# butt_blaster_mk_2.net
KiCad netlist of a schematic drawn in EAGLE
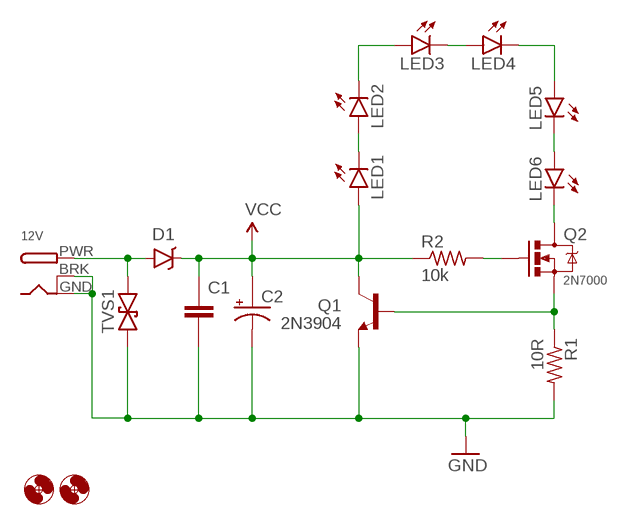
[diagram p0: schematic, sheet 1]

(export (version "E")
  (design (tool "Eeschema 10.0.6"))
  (components
    (comp (ref "12V")
      (value "DCBARRELPTH")
      (footprint "eagle-import:DCJACK_2MM_PTH")
      (libsource (lib "eagle-import") (part "DCBARRELPTH"))
    )
    (comp (ref "C1")
      (value "CAPACITOR-CERAMIC025-024X044")
      (footprint "eagle-import:C025-024X044")
      (libsource (lib "eagle-import") (part "CAPACITOR-CERAMIC025-024X044"))
    )
    (comp (ref "C2")
      (value "CAPACITOR-POLARIZEDE2.5-6")
      (footprint "eagle-import:E2,5-6")
      (libsource (lib "eagle-import") (part "CAPACITOR-POLARIZEDE2.5-6"))
    )
    (comp (ref "D1")
      (value "DIODE-SCHOTTKYPTH-8.38MM")
      (footprint "eagle-import:DIODE-8.38MM")
      (libsource (lib "eagle-import") (part "DIODE-SCHOTTKYPTH-8.38MM"))
    )
    (comp (ref "H1")
      (value "HOLE#2")
      (footprint "eagle-import:HOLE-#2")
      (libsource (lib "eagle-import") (part "HOLE#2"))
    )
    (comp (ref "H2")
      (value "HOLE#2")
      (footprint "eagle-import:HOLE-#2")
      (libsource (lib "eagle-import") (part "HOLE#2"))
    )
    (comp (ref "LED1")
      (value "LED5MM_SHORTPADS")
      (footprint "eagle-import:LED5MM_SHORTPADS")
      (libsource (lib "eagle-import") (part "LED5MM_SHORTPADS"))
    )
    (comp (ref "LED2")
      (value "LED5MM_SHORTPADS")
      (footprint "eagle-import:LED5MM_SHORTPADS")
      (libsource (lib "eagle-import") (part "LED5MM_SHORTPADS"))
    )
    (comp (ref "LED3")
      (value "LED5MM_SHORTPADS")
      (footprint "eagle-import:LED5MM_SHORTPADS")
      (libsource (lib "eagle-import") (part "LED5MM_SHORTPADS"))
    )
    (comp (ref "LED4")
      (value "LED5MM_SHORTPADS")
      (footprint "eagle-import:LED5MM_SHORTPADS")
      (libsource (lib "eagle-import") (part "LED5MM_SHORTPADS"))
    )
    (comp (ref "LED5")
      (value "LED5MM_SHORTPADS")
      (footprint "eagle-import:LED5MM_SHORTPADS")
      (libsource (lib "eagle-import") (part "LED5MM_SHORTPADS"))
    )
    (comp (ref "LED6")
      (value "LED5MM_SHORTPADS")
      (footprint "eagle-import:LED5MM_SHORTPADS")
      (libsource (lib "eagle-import") (part "LED5MM_SHORTPADS"))
    )
    (comp (ref "Q1")
      (value "2N3904")
      (footprint "eagle-import:TO-92-AMMO")
      (libsource (lib "eagle-import") (part "TRANSISTOR_NPNTO-92-AMMO-EBC"))
    )
    (comp (ref "Q2")
      (value "2N7000")
      (footprint "eagle-import:TO-92-AMMO")
      (libsource (lib "eagle-import") (part "MOSFET-NCHANNEL2N7000-AMMO"))
    )
    (comp (ref "R1")
      (value "10R")
      (footprint "eagle-import:RESISTOR-AXIAL-PTH-7.68MM")
      (libsource (lib "eagle-import") (part "RESISTORPTH-AXIAL-7.68MM"))
    )
    (comp (ref "R2")
      (value "10k")
      (footprint "eagle-import:RESISTOR-AXIAL-PTH-7.68MM")
      (libsource (lib "eagle-import") (part "RESISTORPTH-AXIAL-7.68MM"))
    )
    (comp (ref "TVS1")
      (value "TVSDO-41-TVS-BIDIRECTIONAL")
      (footprint "eagle-import:DO-41-TVS")
      (libsource (lib "eagle-import") (part "TVSDO-41-TVS-BIDIRECTIONAL"))
    )
  )
  (nets
    (net (code "1") (name "GND") (class "Default")
      (node (ref "12V") (pin "BRK") (pinfunction "BRK_BRK") (pintype "power_in"))
      (node (ref "12V") (pin "GND") (pinfunction "GND_GND") (pintype "power_in"))
      (node (ref "C1") (pin "2") (pinfunction "2_2") (pintype "passive"))
      (node (ref "C2") (pin "-") (pinfunction "-_-") (pintype "passive"))
      (node (ref "Q1") (pin "1") (pinfunction "E_1") (pintype "passive"))
      (node (ref "R1") (pin "P$2") (pinfunction "2_P$2") (pintype "passive"))
      (node (ref "TVS1") (pin "P$1") (pinfunction "1_P$1") (pintype "passive"))
    )
    (net (code "2") (name "Net-(LED1-C)") (class "Default")
      (node (ref "LED1") (pin "K") (pinfunction "C_K") (pintype "passive"))
      (node (ref "LED2") (pin "A") (pinfunction "A_A") (pintype "passive"))
    )
    (net (code "3") (name "Net-(LED2-C)") (class "Default")
      (node (ref "LED2") (pin "K") (pinfunction "C_K") (pintype "passive"))
      (node (ref "LED3") (pin "A") (pinfunction "A_A") (pintype "passive"))
    )
    (net (code "4") (name "Net-(LED3-C)") (class "Default")
      (node (ref "LED3") (pin "K") (pinfunction "C_K") (pintype "passive"))
      (node (ref "LED4") (pin "A") (pinfunction "A_A") (pintype "passive"))
    )
    (net (code "5") (name "Net-(LED4-C)") (class "Default")
      (node (ref "LED4") (pin "K") (pinfunction "C_K") (pintype "passive"))
      (node (ref "LED5") (pin "A") (pinfunction "A_A") (pintype "passive"))
    )
    (net (code "6") (name "Net-(LED5-C)") (class "Default")
      (node (ref "LED5") (pin "K") (pinfunction "C_K") (pintype "passive"))
      (node (ref "LED6") (pin "A") (pinfunction "A_A") (pintype "passive"))
    )
    (net (code "7") (name "Net-(LED6-C)") (class "Default")
      (node (ref "LED6") (pin "K") (pinfunction "C_K") (pintype "passive"))
      (node (ref "Q2") (pin "3") (pinfunction "D_3") (pintype "passive"))
    )
    (net (code "8") (name "Net-(Q1-B)") (class "Default")
      (node (ref "Q1") (pin "2") (pinfunction "B_2") (pintype "passive"))
      (node (ref "Q2") (pin "1") (pinfunction "S_1") (pintype "passive"))
      (node (ref "R1") (pin "P$1") (pinfunction "1_P$1") (pintype "passive"))
    )
    (net (code "9") (name "Net-(Q2-G)") (class "Default")
      (node (ref "Q2") (pin "2") (pinfunction "G_2") (pintype "passive"))
      (node (ref "R2") (pin "P$2") (pinfunction "2_P$2") (pintype "passive"))
    )
    (net (code "10") (name "Net-(TVS1-2)") (class "Default")
      (node (ref "12V") (pin "PWR") (pinfunction "PWR_PWR") (pintype "power_in"))
      (node (ref "D1") (pin "A") (pinfunction "A_A") (pintype "passive"))
      (node (ref "TVS1") (pin "P$2") (pinfunction "2_P$2") (pintype "passive"))
    )
    (net (code "11") (name "VCC") (class "Default")
      (node (ref "C1") (pin "1") (pinfunction "1_1") (pintype "passive"))
      (node (ref "C2") (pin "+") (pinfunction "+_+") (pintype "passive"))
      (node (ref "D1") (pin "K") (pinfunction "C_K") (pintype "passive"))
      (node (ref "LED1") (pin "A") (pinfunction "A_A") (pintype "passive"))
      (node (ref "Q1") (pin "3") (pinfunction "C_3") (pintype "passive"))
      (node (ref "R2") (pin "P$1") (pinfunction "1_P$1") (pintype "passive"))
    )
  )
)
